# sch_epm.net
KiCad netlist of a schematic drawn in Altium Designer
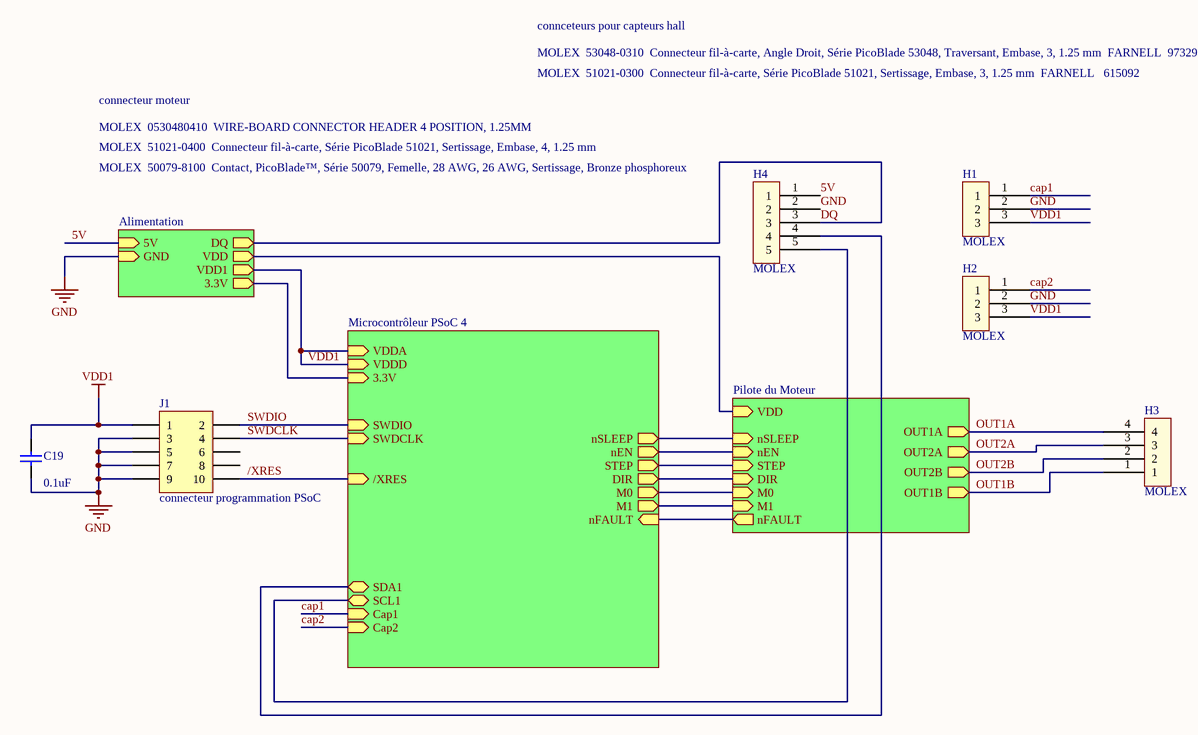
[diagram p0: sch_epm.SchDoc]

(export (version "E")
  (design (tool "Eeschema 10.0.6"))
  (components
    (comp (ref "C19")
      (value "0.1uF")
      (footprint "C1206")
      (description "Capacitor (Semiconductor SIM Model)")
      (fields (field (name "PUBLISHER") "Altium Limited"))
      (libsource (lib "Miscellaneous Devices") (part "Cap Semi"))
    )
    (comp (ref "H1")
      (value "MOLEX")
      (footprint "molex_male_3_broches")
      (description "MOLEX-53048-0510_FARNELL_9732918")
      (libsource (lib "EYE-SAT_EPM_lib") (part "Molex Male 3 broches"))
    )
    (comp (ref "H2")
      (value "MOLEX")
      (footprint "molex_male_3_broches")
      (description "MOLEX-53048-0510_FARNELL_9732918")
      (libsource (lib "EYE-SAT_EPM_lib") (part "Molex Male 3 broches"))
    )
    (comp (ref "H3")
      (value "MOLEX")
      (footprint "molex_male_4_broches")
      (description "MOLEX-53048-0510_FARNELL_2064326")
      (libsource (lib "EYE-SAT_EPM_lib") (part "Molex Male 4 broches_1"))
    )
    (comp (ref "H4")
      (value "MOLEX")
      (footprint "molex_male_5_broches")
      (description "MOLEX-53048-0510_FARNELL_2064326")
      (libsource (lib "EYE-SAT_EPM_lib") (part "Molex Male 5 broches"))
    )
    (comp (ref "J1")
      (value "connecteur programmation PSoC")
      (footprint "50MIL_KEYED_SMD")
      (description "Header, 5-Pin, Dual row")
      (fields (field (name "PUBLISHER") "Altium Limited"))
      (libsource (lib "SCH_LIB_EPM") (part "Header 5X2"))
    )
  )
  (nets
    (net (code "2") (name "/5V") (class "Default")
      (node (ref "H4") (pin "1") (pinfunction "1_1") (pintype "passive"))
    )
    (net (code "4") (name "/DQ") (class "Default")
      (node (ref "H4") (pin "3") (pinfunction "3_3") (pintype "passive"))
    )
    (net (code "7") (name "/OUT1A") (class "Default")
      (node (ref "H3") (pin "4") (pinfunction "4_4") (pintype "passive"))
    )
    (net (code "8") (name "/OUT1B") (class "Default")
      (node (ref "H3") (pin "1") (pinfunction "1_1") (pintype "passive"))
    )
    (net (code "9") (name "/OUT2A") (class "Default")
      (node (ref "H3") (pin "3") (pinfunction "3_3") (pintype "passive"))
    )
    (net (code "10") (name "/OUT2B") (class "Default")
      (node (ref "H3") (pin "2") (pinfunction "2_2") (pintype "passive"))
    )
    (net (code "11") (name "/SCL1") (class "Default")
      (node (ref "H4") (pin "5") (pinfunction "5_5") (pintype "passive"))
    )
    (net (code "12") (name "/SDA1") (class "Default")
      (node (ref "H4") (pin "4") (pinfunction "4_4") (pintype "passive"))
    )
    (net (code "14") (name "/SWDCLK") (class "Default")
      (node (ref "J1") (pin "4") (pinfunction "4_4") (pintype "passive"))
    )
    (net (code "15") (name "/SWDIO") (class "Default")
      (node (ref "J1") (pin "2") (pinfunction "2_2") (pintype "passive"))
    )
    (net (code "17") (name "/cap1") (class "Default")
      (node (ref "H1") (pin "1") (pinfunction "1_1") (pintype "passive"))
    )
    (net (code "18") (name "/cap2") (class "Default")
      (node (ref "H2") (pin "1") (pinfunction "1_1") (pintype "passive"))
    )
    (net (code "22") (name "/{slash}XRES") (class "Default")
      (node (ref "J1") (pin "10") (pinfunction "10_10") (pintype "passive"))
    )
    (net (code "23") (name "GND") (class "Default")
      (node (ref "C19") (pin "1") (pinfunction "1_1") (pintype "passive"))
      (node (ref "H1") (pin "2") (pinfunction "2_2") (pintype "passive"))
      (node (ref "H2") (pin "2") (pinfunction "2_2") (pintype "passive"))
      (node (ref "H4") (pin "2") (pinfunction "2_2") (pintype "passive"))
      (node (ref "J1") (pin "3") (pinfunction "3_3") (pintype "passive"))
      (node (ref "J1") (pin "5") (pinfunction "5_5") (pintype "passive"))
      (node (ref "J1") (pin "7") (pinfunction "7_7") (pintype "passive"))
      (node (ref "J1") (pin "9") (pinfunction "9_9") (pintype "passive"))
    )
    (net (code "24") (name "VDD1") (class "Default")
      (node (ref "C19") (pin "2") (pinfunction "2_2") (pintype "passive"))
      (node (ref "H1") (pin "3") (pinfunction "3_3") (pintype "passive"))
      (node (ref "H2") (pin "3") (pinfunction "3_3") (pintype "passive"))
      (node (ref "J1") (pin "1") (pinfunction "1_1") (pintype "passive"))
    )
    (net (code "25") (name "unconnected-(J1-Pad6)") (class "Default")
      (node (ref "J1") (pin "6") (pinfunction "6_6") (pintype "passive"))
    )
    (net (code "26") (name "unconnected-(J1-Pad8)") (class "Default")
      (node (ref "J1") (pin "8") (pinfunction "8_8") (pintype "passive"))
    )
  )
)
